# sensor_board.net
KiCad netlist of a schematic drawn in EAGLE
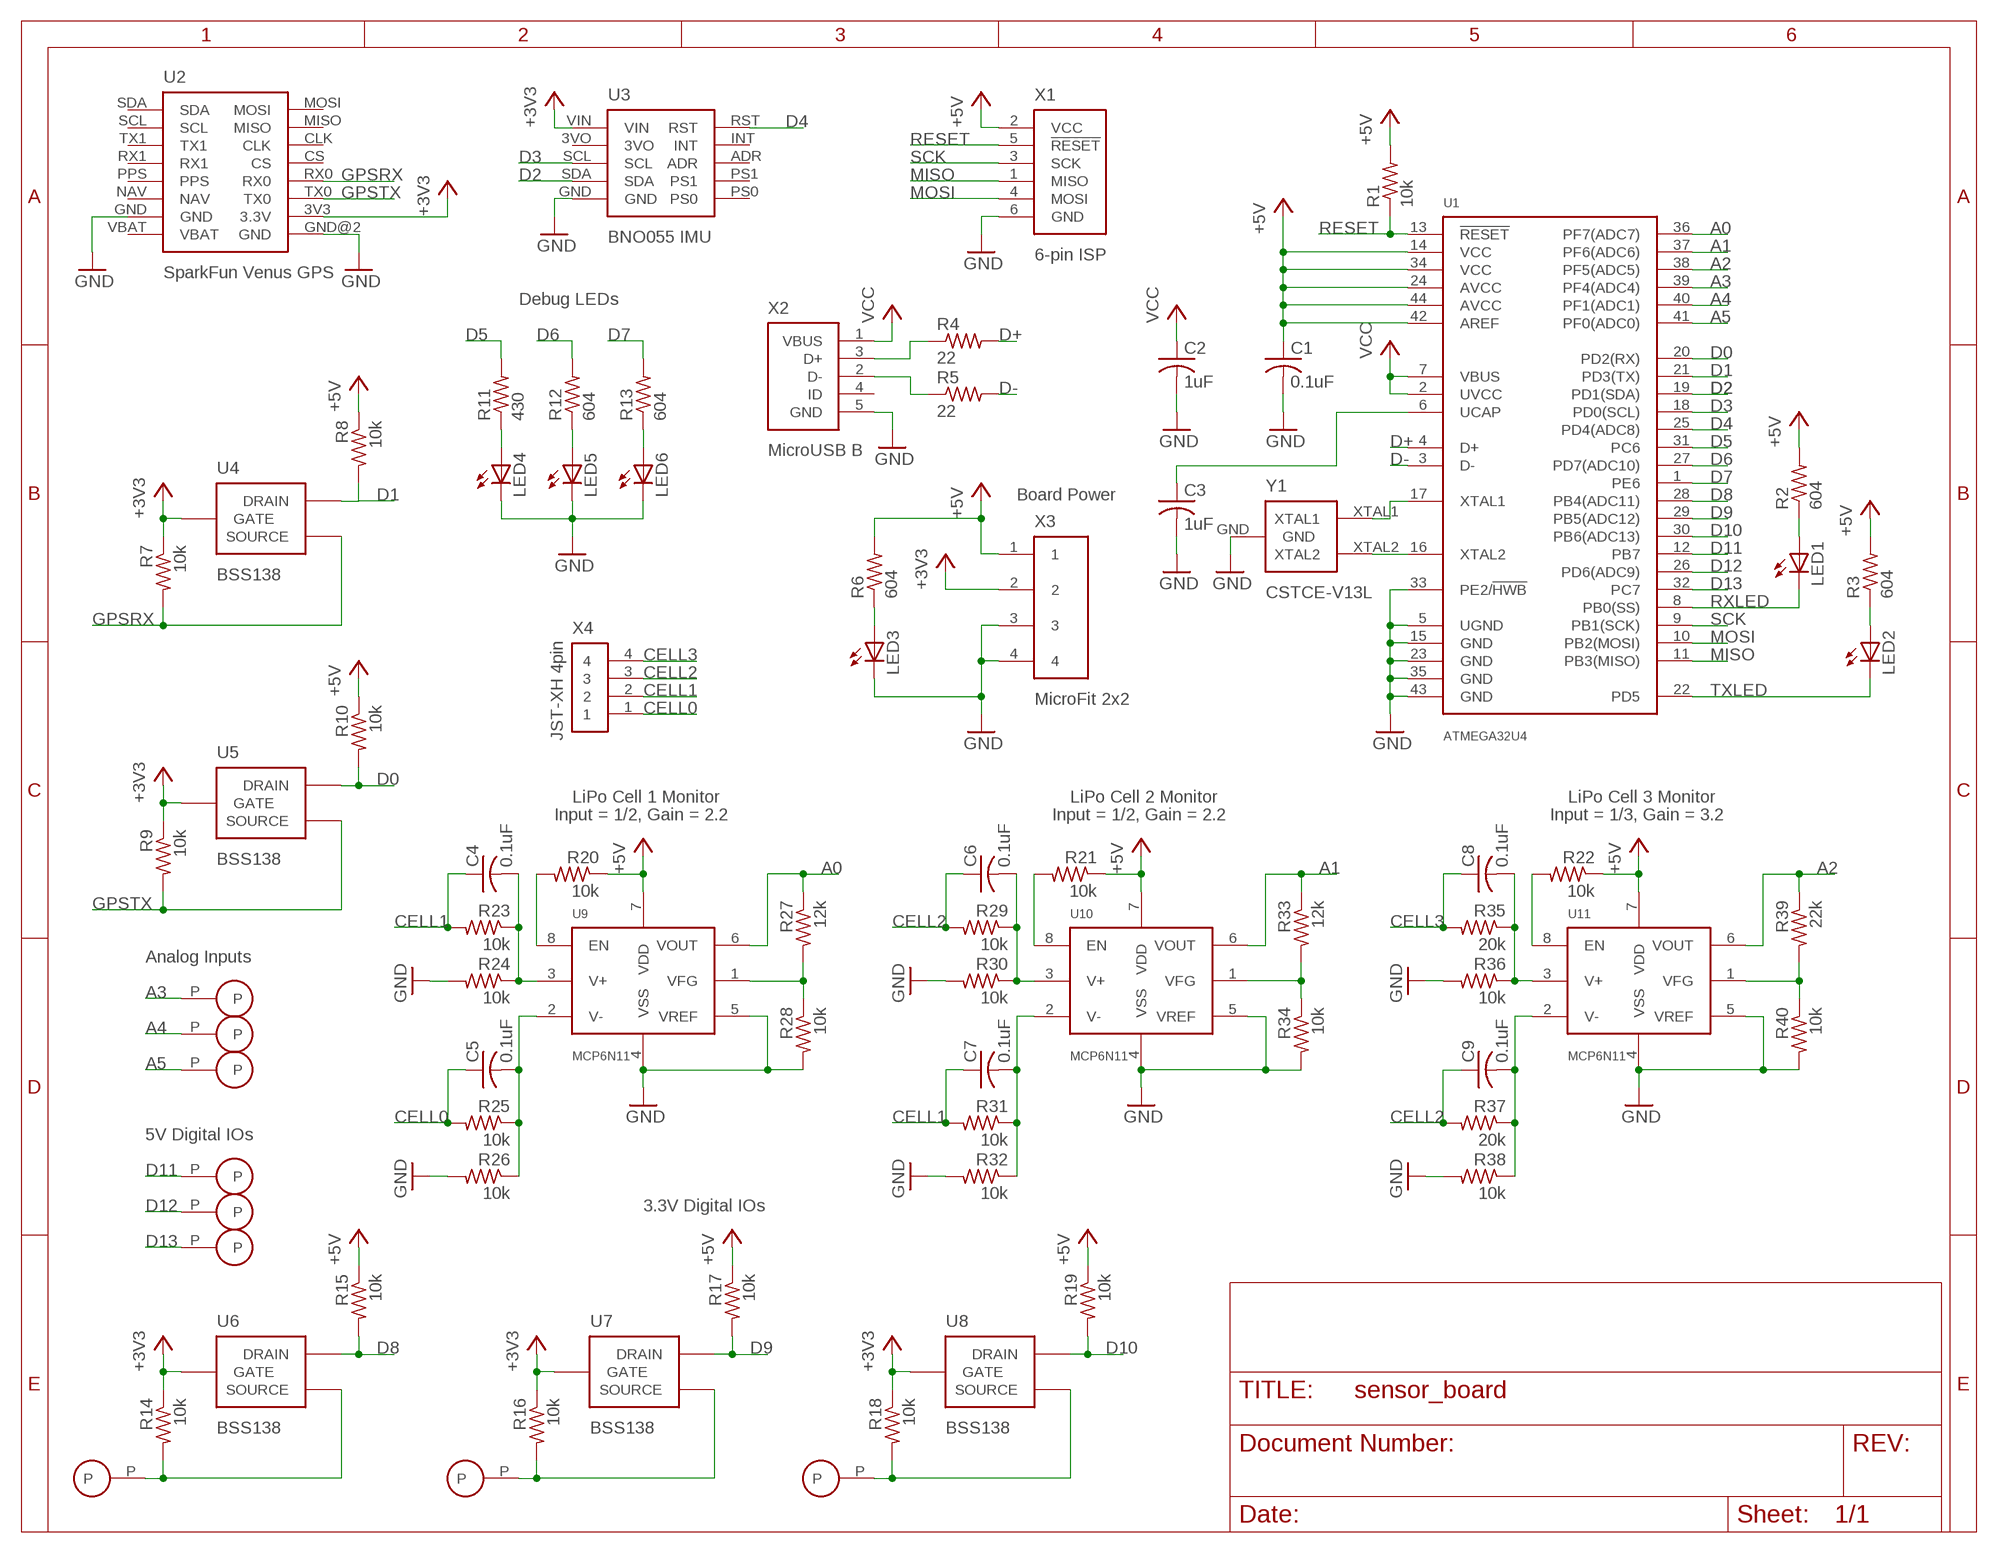
[diagram p0: schematic, sheet 1]

(export (version "E")
  (design (tool "Eeschema 10.0.6"))
  (components
    (comp (ref "C1")
      (value "0.1uF")
      (footprint "eagle-import:C0603")
      (libsource (lib "eagle-import") (part "C-USC0603"))
    )
    (comp (ref "C2")
      (value "1uF")
      (footprint "eagle-import:C0603")
      (libsource (lib "eagle-import") (part "C-USC0603"))
    )
    (comp (ref "C3")
      (value "1uF")
      (footprint "eagle-import:C0603")
      (libsource (lib "eagle-import") (part "C-USC0603"))
    )
    (comp (ref "C4")
      (value "0.1uF")
      (footprint "eagle-import:C0603")
      (libsource (lib "eagle-import") (part "C-USC0603"))
    )
    (comp (ref "C5")
      (value "0.1uF")
      (footprint "eagle-import:C0603")
      (libsource (lib "eagle-import") (part "C-USC0603"))
    )
    (comp (ref "C6")
      (value "0.1uF")
      (footprint "eagle-import:C0603")
      (libsource (lib "eagle-import") (part "C-USC0603"))
    )
    (comp (ref "C7")
      (value "0.1uF")
      (footprint "eagle-import:C0603")
      (libsource (lib "eagle-import") (part "C-USC0603"))
    )
    (comp (ref "C8")
      (value "0.1uF")
      (footprint "eagle-import:C0603")
      (libsource (lib "eagle-import") (part "C-USC0603"))
    )
    (comp (ref "C9")
      (value "0.1uF")
      (footprint "eagle-import:C0603")
      (libsource (lib "eagle-import") (part "C-USC0603"))
    )
    (comp (ref "LED1")
      (value "LEDCHIPLED_0603")
      (footprint "eagle-import:CHIPLED_0603")
      (libsource (lib "eagle-import") (part "LEDCHIPLED_0603"))
    )
    (comp (ref "LED2")
      (value "LEDCHIPLED_0603")
      (footprint "eagle-import:CHIPLED_0603")
      (libsource (lib "eagle-import") (part "LEDCHIPLED_0603"))
    )
    (comp (ref "LED3")
      (value "LEDCHIPLED_0603")
      (footprint "eagle-import:CHIPLED_0603")
      (libsource (lib "eagle-import") (part "LEDCHIPLED_0603"))
    )
    (comp (ref "LED4")
      (value "LEDCHIPLED_0603")
      (footprint "eagle-import:CHIPLED_0603")
      (libsource (lib "eagle-import") (part "LEDCHIPLED_0603"))
    )
    (comp (ref "LED5")
      (value "LEDCHIPLED_0603")
      (footprint "eagle-import:CHIPLED_0603")
      (libsource (lib "eagle-import") (part "LEDCHIPLED_0603"))
    )
    (comp (ref "LED6")
      (value "LEDCHIPLED_0603")
      (footprint "eagle-import:CHIPLED_0603")
      (libsource (lib "eagle-import") (part "LEDCHIPLED_0603"))
    )
    (comp (ref "P1")
      (value "100MIL-PAD")
      (footprint "eagle-import:100MIL-PAD")
      (libsource (lib "eagle-import") (part "100MIL-PAD"))
    )
    (comp (ref "P2")
      (value "100MIL-PAD")
      (footprint "eagle-import:100MIL-PAD")
      (libsource (lib "eagle-import") (part "100MIL-PAD"))
    )
    (comp (ref "P3")
      (value "100MIL-PAD")
      (footprint "eagle-import:100MIL-PAD")
      (libsource (lib "eagle-import") (part "100MIL-PAD"))
    )
    (comp (ref "P4")
      (value "100MIL-PAD")
      (footprint "eagle-import:100MIL-PAD")
      (libsource (lib "eagle-import") (part "100MIL-PAD"))
    )
    (comp (ref "P5")
      (value "100MIL-PAD")
      (footprint "eagle-import:100MIL-PAD")
      (libsource (lib "eagle-import") (part "100MIL-PAD"))
    )
    (comp (ref "P6")
      (value "100MIL-PAD")
      (footprint "eagle-import:100MIL-PAD")
      (libsource (lib "eagle-import") (part "100MIL-PAD"))
    )
    (comp (ref "P8")
      (value "100MIL-PAD")
      (footprint "eagle-import:100MIL-PAD")
      (libsource (lib "eagle-import") (part "100MIL-PAD"))
    )
    (comp (ref "P9")
      (value "100MIL-PAD")
      (footprint "eagle-import:100MIL-PAD")
      (libsource (lib "eagle-import") (part "100MIL-PAD"))
    )
    (comp (ref "P10")
      (value "100MIL-PAD")
      (footprint "eagle-import:100MIL-PAD")
      (libsource (lib "eagle-import") (part "100MIL-PAD"))
    )
    (comp (ref "R1")
      (value "10k")
      (footprint "eagle-import:R0603")
      (libsource (lib "eagle-import") (part "R-US_R0603"))
    )
    (comp (ref "R2")
      (value "604")
      (footprint "eagle-import:R0603")
      (libsource (lib "eagle-import") (part "R-US_R0603"))
    )
    (comp (ref "R3")
      (value "604")
      (footprint "eagle-import:R0603")
      (libsource (lib "eagle-import") (part "R-US_R0603"))
    )
    (comp (ref "R4")
      (value "22")
      (footprint "eagle-import:R0603")
      (libsource (lib "eagle-import") (part "R-US_R0603"))
    )
    (comp (ref "R5")
      (value "22")
      (footprint "eagle-import:R0603")
      (libsource (lib "eagle-import") (part "R-US_R0603"))
    )
    (comp (ref "R6")
      (value "604")
      (footprint "eagle-import:R0603")
      (libsource (lib "eagle-import") (part "R-US_R0603"))
    )
    (comp (ref "R7")
      (value "10k")
      (footprint "eagle-import:R0603")
      (libsource (lib "eagle-import") (part "R-US_R0603"))
    )
    (comp (ref "R8")
      (value "10k")
      (footprint "eagle-import:R0603")
      (libsource (lib "eagle-import") (part "R-US_R0603"))
    )
    (comp (ref "R9")
      (value "10k")
      (footprint "eagle-import:R0603")
      (libsource (lib "eagle-import") (part "R-US_R0603"))
    )
    (comp (ref "R10")
      (value "10k")
      (footprint "eagle-import:R0603")
      (libsource (lib "eagle-import") (part "R-US_R0603"))
    )
    (comp (ref "R11")
      (value "430")
      (footprint "eagle-import:R0603")
      (libsource (lib "eagle-import") (part "R-US_R0603"))
    )
    (comp (ref "R12")
      (value "604")
      (footprint "eagle-import:R0603")
      (libsource (lib "eagle-import") (part "R-US_R0603"))
    )
    (comp (ref "R13")
      (value "604")
      (footprint "eagle-import:R0603")
      (libsource (lib "eagle-import") (part "R-US_R0603"))
    )
    (comp (ref "R14")
      (value "10k")
      (footprint "eagle-import:R0603")
      (libsource (lib "eagle-import") (part "R-US_R0603"))
    )
    (comp (ref "R15")
      (value "10k")
      (footprint "eagle-import:R0603")
      (libsource (lib "eagle-import") (part "R-US_R0603"))
    )
    (comp (ref "R16")
      (value "10k")
      (footprint "eagle-import:R0603")
      (libsource (lib "eagle-import") (part "R-US_R0603"))
    )
    (comp (ref "R17")
      (value "10k")
      (footprint "eagle-import:R0603")
      (libsource (lib "eagle-import") (part "R-US_R0603"))
    )
    (comp (ref "R18")
      (value "10k")
      (footprint "eagle-import:R0603")
      (libsource (lib "eagle-import") (part "R-US_R0603"))
    )
    (comp (ref "R19")
      (value "10k")
      (footprint "eagle-import:R0603")
      (libsource (lib "eagle-import") (part "R-US_R0603"))
    )
    (comp (ref "R20")
      (value "10k")
      (footprint "eagle-import:R0603")
      (libsource (lib "eagle-import") (part "R-US_R0603"))
    )
    (comp (ref "R21")
      (value "10k")
      (footprint "eagle-import:R0603")
      (libsource (lib "eagle-import") (part "R-US_R0603"))
    )
    (comp (ref "R22")
      (value "10k")
      (footprint "eagle-import:R0603")
      (libsource (lib "eagle-import") (part "R-US_R0603"))
    )
    (comp (ref "R23")
      (value "10k")
      (footprint "eagle-import:R0603")
      (libsource (lib "eagle-import") (part "R-US_R0603"))
    )
    (comp (ref "R24")
      (value "10k")
      (footprint "eagle-import:R0603")
      (libsource (lib "eagle-import") (part "R-US_R0603"))
    )
    (comp (ref "R25")
      (value "10k")
      (footprint "eagle-import:R0603")
      (libsource (lib "eagle-import") (part "R-US_R0603"))
    )
    (comp (ref "R26")
      (value "10k")
      (footprint "eagle-import:R0603")
      (libsource (lib "eagle-import") (part "R-US_R0603"))
    )
    (comp (ref "R27")
      (value "12k")
      (footprint "eagle-import:R0603")
      (libsource (lib "eagle-import") (part "R-US_R0603"))
    )
    (comp (ref "R28")
      (value "10k")
      (footprint "eagle-import:R0603")
      (libsource (lib "eagle-import") (part "R-US_R0603"))
    )
    (comp (ref "R29")
      (value "10k")
      (footprint "eagle-import:R0603")
      (libsource (lib "eagle-import") (part "R-US_R0603"))
    )
    (comp (ref "R30")
      (value "10k")
      (footprint "eagle-import:R0603")
      (libsource (lib "eagle-import") (part "R-US_R0603"))
    )
    (comp (ref "R31")
      (value "10k")
      (footprint "eagle-import:R0603")
      (libsource (lib "eagle-import") (part "R-US_R0603"))
    )
    (comp (ref "R32")
      (value "10k")
      (footprint "eagle-import:R0603")
      (libsource (lib "eagle-import") (part "R-US_R0603"))
    )
    (comp (ref "R33")
      (value "12k")
      (footprint "eagle-import:R0603")
      (libsource (lib "eagle-import") (part "R-US_R0603"))
    )
    (comp (ref "R34")
      (value "10k")
      (footprint "eagle-import:R0603")
      (libsource (lib "eagle-import") (part "R-US_R0603"))
    )
    (comp (ref "R35")
      (value "20k")
      (footprint "eagle-import:R0603")
      (libsource (lib "eagle-import") (part "R-US_R0603"))
    )
    (comp (ref "R36")
      (value "10k")
      (footprint "eagle-import:R0603")
      (libsource (lib "eagle-import") (part "R-US_R0603"))
    )
    (comp (ref "R37")
      (value "20k")
      (footprint "eagle-import:R0603")
      (libsource (lib "eagle-import") (part "R-US_R0603"))
    )
    (comp (ref "R38")
      (value "10k")
      (footprint "eagle-import:R0603")
      (libsource (lib "eagle-import") (part "R-US_R0603"))
    )
    (comp (ref "R39")
      (value "22k")
      (footprint "eagle-import:R0603")
      (libsource (lib "eagle-import") (part "R-US_R0603"))
    )
    (comp (ref "R40")
      (value "10k")
      (footprint "eagle-import:R0603")
      (libsource (lib "eagle-import") (part "R-US_R0603"))
    )
    (comp (ref "U1")
      (value "ATMEGA32U4")
      (footprint "eagle-import:TQFP-44")
      (libsource (lib "eagle-import") (part "ATMEGA32U4"))
    )
    (comp (ref "U2")
      (value "SPARKFUN-VENUS-GPS")
      (footprint "eagle-import:SPARKFUN-VENUS-GPS")
      (libsource (lib "eagle-import") (part "SPARKFUN-VENUS-GPS"))
    )
    (comp (ref "U3")
      (value "ADAFRUIT-BNO055-IMU")
      (footprint "eagle-import:ADAFRUIT-BNO055-IMU")
      (libsource (lib "eagle-import") (part "ADAFRUIT-BNO055-IMU"))
    )
    (comp (ref "U4")
      (value "BSS138")
      (footprint "eagle-import:SOT-23")
      (libsource (lib "eagle-import") (part "BSS138"))
    )
    (comp (ref "U5")
      (value "BSS138")
      (footprint "eagle-import:SOT-23")
      (libsource (lib "eagle-import") (part "BSS138"))
    )
    (comp (ref "U6")
      (value "BSS138")
      (footprint "eagle-import:SOT-23")
      (libsource (lib "eagle-import") (part "BSS138"))
    )
    (comp (ref "U7")
      (value "BSS138")
      (footprint "eagle-import:SOT-23")
      (libsource (lib "eagle-import") (part "BSS138"))
    )
    (comp (ref "U8")
      (value "BSS138")
      (footprint "eagle-import:SOT-23")
      (libsource (lib "eagle-import") (part "BSS138"))
    )
    (comp (ref "U9")
      (value "MCP6N11")
      (footprint "eagle-import:SOIC-8")
      (libsource (lib "eagle-import") (part "MCP6N11"))
    )
    (comp (ref "U10")
      (value "MCP6N11")
      (footprint "eagle-import:SOIC-8")
      (libsource (lib "eagle-import") (part "MCP6N11"))
    )
    (comp (ref "U11")
      (value "MCP6N11")
      (footprint "eagle-import:SOIC-8")
      (libsource (lib "eagle-import") (part "MCP6N11"))
    )
    (comp (ref "X1")
      (value "ISP-HEADER")
      (footprint "eagle-import:ISP-HEADER")
      (libsource (lib "eagle-import") (part "ISP-HEADER"))
    )
    (comp (ref "X2")
      (value "MICRO-USB-B")
      (footprint "eagle-import:MICRO-USB-B")
      (libsource (lib "eagle-import") (part "MICRO-USB-B"))
    )
    (comp (ref "X3")
      (value "MICROFIT-2X2-SMD")
      (footprint "eagle-import:MICROFIT-2X2-0430450411")
      (libsource (lib "eagle-import") (part "MICROFIT-2X2-SMD"))
    )
    (comp (ref "X4")
      (value "JST-XH-4")
      (footprint "eagle-import:JST-XH-4")
      (libsource (lib "eagle-import") (part "JST-XH-4"))
    )
    (comp (ref "Y1")
      (value "CSTCE-V13L")
      (footprint "eagle-import:CSTCE-V13L")
      (libsource (lib "eagle-import") (part "CSTCE-V13L"))
    )
  )
  (nets
    (net (code "1") (name "+3V3") (class "Default")
      (node (ref "R14") (pin "1") (pinfunction "1_1") (pintype "passive"))
      (node (ref "R16") (pin "1") (pinfunction "1_1") (pintype "passive"))
      (node (ref "R18") (pin "1") (pinfunction "1_1") (pintype "passive"))
      (node (ref "R7") (pin "1") (pinfunction "1_1") (pintype "passive"))
      (node (ref "R9") (pin "1") (pinfunction "1_1") (pintype "passive"))
      (node (ref "U2") (pin "3V3") (pinfunction "3.3V_3V3") (pintype "power_in"))
      (node (ref "U3") (pin "VIN") (pinfunction "VIN_VIN") (pintype "power_in"))
      (node (ref "U4") (pin "GATE") (pinfunction "GATE_GATE") (pintype "bidirectional"))
      (node (ref "U5") (pin "GATE") (pinfunction "GATE_GATE") (pintype "bidirectional"))
      (node (ref "U6") (pin "GATE") (pinfunction "GATE_GATE") (pintype "bidirectional"))
      (node (ref "U7") (pin "GATE") (pinfunction "GATE_GATE") (pintype "bidirectional"))
      (node (ref "U8") (pin "GATE") (pinfunction "GATE_GATE") (pintype "bidirectional"))
      (node (ref "X3") (pin "2") (pinfunction "2_2") (pintype "bidirectional"))
    )
    (net (code "2") (name "+5V") (class "Default")
      (node (ref "C1") (pin "1") (pinfunction "1_1") (pintype "passive"))
      (node (ref "R1") (pin "2") (pinfunction "2_2") (pintype "passive"))
      (node (ref "R10") (pin "1") (pinfunction "1_1") (pintype "passive"))
      (node (ref "R15") (pin "1") (pinfunction "1_1") (pintype "passive"))
      (node (ref "R17") (pin "1") (pinfunction "1_1") (pintype "passive"))
      (node (ref "R19") (pin "1") (pinfunction "1_1") (pintype "passive"))
      (node (ref "R2") (pin "2") (pinfunction "2_2") (pintype "passive"))
      (node (ref "R20") (pin "1") (pinfunction "1_1") (pintype "passive"))
      (node (ref "R21") (pin "1") (pinfunction "1_1") (pintype "passive"))
      (node (ref "R22") (pin "1") (pinfunction "1_1") (pintype "passive"))
      (node (ref "R3") (pin "2") (pinfunction "2_2") (pintype "passive"))
      (node (ref "R6") (pin "2") (pinfunction "2_2") (pintype "passive"))
      (node (ref "R8") (pin "1") (pinfunction "1_1") (pintype "passive"))
      (node (ref "U1") (pin "14") (pinfunction "VCC_14") (pintype "power_in"))
      (node (ref "U1") (pin "24") (pinfunction "AVCC_24") (pintype "power_in"))
      (node (ref "U1") (pin "34") (pinfunction "VCC_34") (pintype "power_in"))
      (node (ref "U1") (pin "42") (pinfunction "AREF_42") (pintype "input"))
      (node (ref "U1") (pin "44") (pinfunction "AVCC_44") (pintype "power_in"))
      (node (ref "U10") (pin "7") (pinfunction "VDD_7") (pintype "power_in"))
      (node (ref "U11") (pin "7") (pinfunction "VDD_7") (pintype "power_in"))
      (node (ref "U9") (pin "7") (pinfunction "VDD_7") (pintype "power_in"))
      (node (ref "X1") (pin "2") (pinfunction "VCC_2") (pintype "power_in"))
      (node (ref "X3") (pin "1") (pinfunction "1_1") (pintype "bidirectional"))
    )
    (net (code "3") (name "/3VO") (class "Default")
      (node (ref "U3") (pin "3VO") (pinfunction "3VO_3VO") (pintype "power_in"))
    )
    (net (code "4") (name "/A0") (class "Default")
      (node (ref "R27") (pin "1") (pinfunction "1_1") (pintype "passive"))
      (node (ref "U1") (pin "36") (pinfunction "PF7(ADC7)_36") (pintype "bidirectional"))
      (node (ref "U9") (pin "6") (pinfunction "VOUT_6") (pintype "bidirectional"))
    )
    (net (code "5") (name "/A1") (class "Default")
      (node (ref "R33") (pin "1") (pinfunction "1_1") (pintype "passive"))
      (node (ref "U1") (pin "37") (pinfunction "PF6(ADC6)_37") (pintype "bidirectional"))
      (node (ref "U10") (pin "6") (pinfunction "VOUT_6") (pintype "bidirectional"))
    )
    (net (code "6") (name "/A2") (class "Default")
      (node (ref "R39") (pin "1") (pinfunction "1_1") (pintype "passive"))
      (node (ref "U1") (pin "38") (pinfunction "PF5(ADC5)_38") (pintype "bidirectional"))
      (node (ref "U11") (pin "6") (pinfunction "VOUT_6") (pintype "bidirectional"))
    )
    (net (code "7") (name "/A3") (class "Default")
      (node (ref "P8") (pin "P") (pinfunction "P_P") (pintype "bidirectional"))
      (node (ref "U1") (pin "39") (pinfunction "PF4(ADC4)_39") (pintype "bidirectional"))
    )
    (net (code "8") (name "/A4") (class "Default")
      (node (ref "P9") (pin "P") (pinfunction "P_P") (pintype "bidirectional"))
      (node (ref "U1") (pin "40") (pinfunction "PF1(ADC1)_40") (pintype "bidirectional"))
    )
    (net (code "9") (name "/A5") (class "Default")
      (node (ref "P10") (pin "P") (pinfunction "P_P") (pintype "bidirectional"))
      (node (ref "U1") (pin "41") (pinfunction "PF0(ADC0)_41") (pintype "bidirectional"))
    )
    (net (code "10") (name "/CELL0") (class "Default")
      (node (ref "C5") (pin "1") (pinfunction "1_1") (pintype "passive"))
      (node (ref "R25") (pin "2") (pinfunction "2_2") (pintype "passive"))
      (node (ref "X4") (pin "1") (pinfunction "1_1") (pintype "bidirectional"))
    )
    (net (code "11") (name "/CELL1") (class "Default")
      (node (ref "C4") (pin "1") (pinfunction "1_1") (pintype "passive"))
      (node (ref "C7") (pin "1") (pinfunction "1_1") (pintype "passive"))
      (node (ref "R23") (pin "2") (pinfunction "2_2") (pintype "passive"))
      (node (ref "R31") (pin "2") (pinfunction "2_2") (pintype "passive"))
      (node (ref "X4") (pin "2") (pinfunction "2_2") (pintype "bidirectional"))
    )
    (net (code "12") (name "/CELL2") (class "Default")
      (node (ref "C6") (pin "1") (pinfunction "1_1") (pintype "passive"))
      (node (ref "C9") (pin "1") (pinfunction "1_1") (pintype "passive"))
      (node (ref "R29") (pin "2") (pinfunction "2_2") (pintype "passive"))
      (node (ref "R37") (pin "2") (pinfunction "2_2") (pintype "passive"))
      (node (ref "X4") (pin "3") (pinfunction "3_3") (pintype "bidirectional"))
    )
    (net (code "13") (name "/CELL3") (class "Default")
      (node (ref "C8") (pin "1") (pinfunction "1_1") (pintype "passive"))
      (node (ref "R35") (pin "2") (pinfunction "2_2") (pintype "passive"))
      (node (ref "X4") (pin "4") (pinfunction "4_4") (pintype "bidirectional"))
    )
    (net (code "14") (name "/D+") (class "Default")
      (node (ref "R4") (pin "2") (pinfunction "2_2") (pintype "passive"))
      (node (ref "U1") (pin "4") (pinfunction "D+_4") (pintype "bidirectional"))
    )
    (net (code "15") (name "/D-") (class "Default")
      (node (ref "R5") (pin "2") (pinfunction "2_2") (pintype "passive"))
      (node (ref "U1") (pin "3") (pinfunction "D-_3") (pintype "bidirectional"))
    )
    (net (code "16") (name "/D0") (class "Default")
      (node (ref "R10") (pin "2") (pinfunction "2_2") (pintype "passive"))
      (node (ref "U1") (pin "20") (pinfunction "PD2(RX)_20") (pintype "bidirectional"))
      (node (ref "U5") (pin "DRAIN") (pinfunction "DRAIN_DRAIN") (pintype "bidirectional"))
    )
    (net (code "17") (name "/D1") (class "Default")
      (node (ref "R8") (pin "2") (pinfunction "2_2") (pintype "passive"))
      (node (ref "U1") (pin "21") (pinfunction "PD3(TX)_21") (pintype "bidirectional"))
      (node (ref "U4") (pin "DRAIN") (pinfunction "DRAIN_DRAIN") (pintype "bidirectional"))
    )
    (net (code "18") (name "/D2") (class "Default")
      (node (ref "U1") (pin "19") (pinfunction "PD1(SDA)_19") (pintype "bidirectional"))
      (node (ref "U3") (pin "SDA") (pinfunction "SDA_SDA") (pintype "bidirectional"))
    )
    (net (code "19") (name "/D3") (class "Default")
      (node (ref "U1") (pin "18") (pinfunction "PD0(SCL)_18") (pintype "bidirectional"))
      (node (ref "U3") (pin "SCL") (pinfunction "SCL_SCL") (pintype "bidirectional"))
    )
    (net (code "20") (name "/D4") (class "Default")
      (node (ref "U1") (pin "25") (pinfunction "PD4(ADC8)_25") (pintype "bidirectional"))
      (node (ref "U3") (pin "RST") (pinfunction "RST_RST") (pintype "bidirectional"))
    )
    (net (code "21") (name "/D5") (class "Default")
      (node (ref "R11") (pin "2") (pinfunction "2_2") (pintype "passive"))
      (node (ref "U1") (pin "31") (pinfunction "PC6_31") (pintype "bidirectional"))
    )
    (net (code "22") (name "/D6") (class "Default")
      (node (ref "R12") (pin "2") (pinfunction "2_2") (pintype "passive"))
      (node (ref "U1") (pin "27") (pinfunction "PD7(ADC10)_27") (pintype "bidirectional"))
    )
    (net (code "23") (name "/D7") (class "Default")
      (node (ref "R13") (pin "2") (pinfunction "2_2") (pintype "passive"))
      (node (ref "U1") (pin "1") (pinfunction "PE6_1") (pintype "bidirectional"))
    )
    (net (code "24") (name "/D8") (class "Default")
      (node (ref "R15") (pin "2") (pinfunction "2_2") (pintype "passive"))
      (node (ref "U1") (pin "28") (pinfunction "PB4(ADC11)_28") (pintype "bidirectional"))
      (node (ref "U6") (pin "DRAIN") (pinfunction "DRAIN_DRAIN") (pintype "bidirectional"))
    )
    (net (code "25") (name "/D9") (class "Default")
      (node (ref "R17") (pin "2") (pinfunction "2_2") (pintype "passive"))
      (node (ref "U1") (pin "29") (pinfunction "PB5(ADC12)_29") (pintype "bidirectional"))
      (node (ref "U7") (pin "DRAIN") (pinfunction "DRAIN_DRAIN") (pintype "bidirectional"))
    )
    (net (code "26") (name "/D10") (class "Default")
      (node (ref "R19") (pin "2") (pinfunction "2_2") (pintype "passive"))
      (node (ref "U1") (pin "30") (pinfunction "PB6(ADC13)_30") (pintype "bidirectional"))
      (node (ref "U8") (pin "DRAIN") (pinfunction "DRAIN_DRAIN") (pintype "bidirectional"))
    )
    (net (code "27") (name "/D11") (class "Default")
      (node (ref "P1") (pin "P") (pinfunction "P_P") (pintype "bidirectional"))
      (node (ref "U1") (pin "12") (pinfunction "PB7_12") (pintype "bidirectional"))
    )
    (net (code "28") (name "/D12") (class "Default")
      (node (ref "P2") (pin "P") (pinfunction "P_P") (pintype "bidirectional"))
      (node (ref "U1") (pin "26") (pinfunction "PD6(ADC9)_26") (pintype "bidirectional"))
    )
    (net (code "29") (name "/D13") (class "Default")
      (node (ref "P3") (pin "P") (pinfunction "P_P") (pintype "bidirectional"))
      (node (ref "U1") (pin "32") (pinfunction "PC7_32") (pintype "bidirectional"))
    )
    (net (code "30") (name "/GPSRX") (class "Default")
      (node (ref "R7") (pin "2") (pinfunction "2_2") (pintype "passive"))
      (node (ref "U2") (pin "RX0") (pinfunction "RX0_RX0") (pintype "bidirectional"))
      (node (ref "U4") (pin "SOURCE") (pinfunction "SOURCE_SOURCE") (pintype "bidirectional"))
    )
    (net (code "31") (name "/GPSTX") (class "Default")
      (node (ref "R9") (pin "2") (pinfunction "2_2") (pintype "passive"))
      (node (ref "U2") (pin "TX0") (pinfunction "TX0_TX0") (pintype "bidirectional"))
      (node (ref "U5") (pin "SOURCE") (pinfunction "SOURCE_SOURCE") (pintype "bidirectional"))
    )
    (net (code "32") (name "/MISO") (class "Default")
      (node (ref "U1") (pin "11") (pinfunction "PB3(MISO)_11") (pintype "bidirectional"))
      (node (ref "X1") (pin "1") (pinfunction "MISO_1") (pintype "bidirectional"))
    )
    (net (code "33") (name "/MOSI") (class "Default")
      (node (ref "U1") (pin "10") (pinfunction "PB2(MOSI)_10") (pintype "bidirectional"))
      (node (ref "X1") (pin "4") (pinfunction "MOSI_4") (pintype "bidirectional"))
    )
    (net (code "34") (name "/RESET") (class "Default")
      (node (ref "R1") (pin "1") (pinfunction "1_1") (pintype "passive"))
      (node (ref "U1") (pin "13") (pinfunction "~{RESET}_13") (pintype "input"))
      (node (ref "X1") (pin "5") (pinfunction "~{RESET}_5") (pintype "bidirectional"))
    )
    (net (code "35") (name "/RXLED") (class "Default")
      (node (ref "LED1") (pin "C") (pinfunction "C_C") (pintype "passive"))
      (node (ref "U1") (pin "8") (pinfunction "PB0(SS)_8") (pintype "bidirectional"))
    )
    (net (code "36") (name "/SCK") (class "Default")
      (node (ref "U1") (pin "9") (pinfunction "PB1(SCK)_9") (pintype "bidirectional"))
      (node (ref "X1") (pin "3") (pinfunction "SCK_3") (pintype "bidirectional"))
    )
    (net (code "37") (name "/TXLED") (class "Default")
      (node (ref "LED2") (pin "C") (pinfunction "C_C") (pintype "passive"))
      (node (ref "U1") (pin "22") (pinfunction "PD5_22") (pintype "bidirectional"))
    )
    (net (code "38") (name "/VBAT") (class "Default")
      (node (ref "U2") (pin "VBAT") (pinfunction "VBAT_VBAT") (pintype "power_in"))
    )
    (net (code "39") (name "GND") (class "Default")
      (node (ref "C1") (pin "2") (pinfunction "2_2") (pintype "passive"))
      (node (ref "C2") (pin "2") (pinfunction "2_2") (pintype "passive"))
      (node (ref "C3") (pin "2") (pinfunction "2_2") (pintype "passive"))
      (node (ref "LED3") (pin "C") (pinfunction "C_C") (pintype "passive"))
      (node (ref "LED4") (pin "C") (pinfunction "C_C") (pintype "passive"))
      (node (ref "LED5") (pin "C") (pinfunction "C_C") (pintype "passive"))
      (node (ref "LED6") (pin "C") (pinfunction "C_C") (pintype "passive"))
      (node (ref "R24") (pin "2") (pinfunction "2_2") (pintype "passive"))
      (node (ref "R26") (pin "2") (pinfunction "2_2") (pintype "passive"))
      (node (ref "R28") (pin "2") (pinfunction "2_2") (pintype "passive"))
      (node (ref "R30") (pin "2") (pinfunction "2_2") (pintype "passive"))
      (node (ref "R32") (pin "2") (pinfunction "2_2") (pintype "passive"))
      (node (ref "R34") (pin "2") (pinfunction "2_2") (pintype "passive"))
      (node (ref "R36") (pin "2") (pinfunction "2_2") (pintype "passive"))
      (node (ref "R38") (pin "2") (pinfunction "2_2") (pintype "passive"))
      (node (ref "R40") (pin "2") (pinfunction "2_2") (pintype "passive"))
      (node (ref "U1") (pin "15") (pinfunction "GND_15") (pintype "power_in"))
      (node (ref "U1") (pin "23") (pinfunction "GND_23") (pintype "power_in"))
      (node (ref "U1") (pin "33") (pinfunction "PE2/~{HWB}_33") (pintype "bidirectional"))
      (node (ref "U1") (pin "35") (pinfunction "GND_35") (pintype "power_in"))
      (node (ref "U1") (pin "43") (pinfunction "GND_43") (pintype "power_in"))
      (node (ref "U1") (pin "5") (pinfunction "UGND_5") (pintype "power_in"))
      (node (ref "U10") (pin "4") (pinfunction "VSS_4") (pintype "power_in"))
      (node (ref "U10") (pin "5") (pinfunction "VREF_5") (pintype "bidirectional"))
      (node (ref "U11") (pin "4") (pinfunction "VSS_4") (pintype "power_in"))
      (node (ref "U11") (pin "5") (pinfunction "VREF_5") (pintype "bidirectional"))
      (node (ref "U2") (pin "GND") (pinfunction "GND_GND") (pintype "power_in"))
      (node (ref "U2") (pin "GND@2") (pinfunction "GND_GND@2") (pintype "power_in"))
      (node (ref "U3") (pin "GND") (pinfunction "GND_GND") (pintype "power_in"))
      (node (ref "U9") (pin "4") (pinfunction "VSS_4") (pintype "power_in"))
      (node (ref "U9") (pin "5") (pinfunction "VREF_5") (pintype "bidirectional"))
      (node (ref "X1") (pin "6") (pinfunction "GND_6") (pintype "power_in"))
      (node (ref "X2") (pin "5") (pinfunction "GND_5") (pintype "power_in"))
      (node (ref "X3") (pin "3") (pinfunction "3_3") (pintype "bidirectional"))
      (node (ref "X3") (pin "4") (pinfunction "4_4") (pintype "bidirectional"))
      (node (ref "Y1") (pin "GND") (pinfunction "GND_GND") (pintype "power_in"))
    )
    (net (code "40") (name "Net-(LED1-PadA)") (class "Default")
      (node (ref "LED1") (pin "A") (pinfunction "A_A") (pintype "passive"))
      (node (ref "R2") (pin "1") (pinfunction "1_1") (pintype "passive"))
    )
    (net (code "41") (name "Net-(LED2-PadA)") (class "Default")
      (node (ref "LED2") (pin "A") (pinfunction "A_A") (pintype "passive"))
      (node (ref "R3") (pin "1") (pinfunction "1_1") (pintype "passive"))
    )
    (net (code "42") (name "Net-(LED3-PadA)") (class "Default")
      (node (ref "LED3") (pin "A") (pinfunction "A_A") (pintype "passive"))
      (node (ref "R6") (pin "1") (pinfunction "1_1") (pintype "passive"))
    )
    (net (code "43") (name "Net-(LED4-PadA)") (class "Default")
      (node (ref "LED4") (pin "A") (pinfunction "A_A") (pintype "passive"))
      (node (ref "R11") (pin "1") (pinfunction "1_1") (pintype "passive"))
    )
    (net (code "44") (name "Net-(LED5-PadA)") (class "Default")
      (node (ref "LED5") (pin "A") (pinfunction "A_A") (pintype "passive"))
      (node (ref "R12") (pin "1") (pinfunction "1_1") (pintype "passive"))
    )
    (net (code "45") (name "Net-(LED6-PadA)") (class "Default")
      (node (ref "LED6") (pin "A") (pinfunction "A_A") (pintype "passive"))
      (node (ref "R13") (pin "1") (pinfunction "1_1") (pintype "passive"))
    )
    (net (code "46") (name "Net-(P4-PadP)") (class "Default")
      (node (ref "P4") (pin "P") (pinfunction "P_P") (pintype "bidirectional"))
      (node (ref "R14") (pin "2") (pinfunction "2_2") (pintype "passive"))
      (node (ref "U6") (pin "SOURCE") (pinfunction "SOURCE_SOURCE") (pintype "bidirectional"))
    )
    (net (code "47") (name "Net-(P5-PadP)") (class "Default")
      (node (ref "P5") (pin "P") (pinfunction "P_P") (pintype "bidirectional"))
      (node (ref "R16") (pin "2") (pinfunction "2_2") (pintype "passive"))
      (node (ref "U7") (pin "SOURCE") (pinfunction "SOURCE_SOURCE") (pintype "bidirectional"))
    )
    (net (code "48") (name "Net-(P6-PadP)") (class "Default")
      (node (ref "P6") (pin "P") (pinfunction "P_P") (pintype "bidirectional"))
      (node (ref "R18") (pin "2") (pinfunction "2_2") (pintype "passive"))
      (node (ref "U8") (pin "SOURCE") (pinfunction "SOURCE_SOURCE") (pintype "bidirectional"))
    )
    (net (code "49") (name "Net-(U1-UCAP)") (class "Default")
      (node (ref "C3") (pin "1") (pinfunction "1_1") (pintype "passive"))
      (node (ref "U1") (pin "6") (pinfunction "UCAP_6") (pintype "bidirectional"))
    )
    (net (code "50") (name "Net-(U1-XTAL1)") (class "Default")
      (node (ref "U1") (pin "17") (pinfunction "XTAL1_17") (pintype "bidirectional"))
      (node (ref "Y1") (pin "XTAL1") (pinfunction "XTAL1_XTAL1") (pintype "bidirectional"))
    )
    (net (code "51") (name "Net-(U1-XTAL2)") (class "Default")
      (node (ref "U1") (pin "16") (pinfunction "XTAL2_16") (pintype "bidirectional"))
      (node (ref "Y1") (pin "XTAL2") (pinfunction "XTAL2_XTAL2") (pintype "bidirectional"))
    )
    (net (code "52") (name "Net-(U9-EN)") (class "Default")
      (node (ref "R20") (pin "2") (pinfunction "2_2") (pintype "passive"))
      (node (ref "U9") (pin "8") (pinfunction "EN_8") (pintype "bidirectional"))
    )
    (net (code "53") (name "Net-(U9-V+)") (class "Default")
      (node (ref "C4") (pin "2") (pinfunction "2_2") (pintype "passive"))
      (node (ref "R23") (pin "1") (pinfunction "1_1") (pintype "passive"))
      (node (ref "R24") (pin "1") (pinfunction "1_1") (pintype "passive"))
      (node (ref "U9") (pin "3") (pinfunction "V+_3") (pintype "bidirectional"))
    )
    (net (code "54") (name "Net-(U9-V-)") (class "Default")
      (node (ref "C5") (pin "2") (pinfunction "2_2") (pintype "passive"))
      (node (ref "R25") (pin "1") (pinfunction "1_1") (pintype "passive"))
      (node (ref "R26") (pin "1") (pinfunction "1_1") (pintype "passive"))
      (node (ref "U9") (pin "2") (pinfunction "V-_2") (pintype "bidirectional"))
    )
    (net (code "55") (name "Net-(U9-VFG)") (class "Default")
      (node (ref "R27") (pin "2") (pinfunction "2_2") (pintype "passive"))
      (node (ref "R28") (pin "1") (pinfunction "1_1") (pintype "passive"))
      (node (ref "U9") (pin "1") (pinfunction "VFG_1") (pintype "bidirectional"))
    )
    (net (code "56") (name "Net-(U10-EN)") (class "Default")
      (node (ref "R21") (pin "2") (pinfunction "2_2") (pintype "passive"))
      (node (ref "U10") (pin "8") (pinfunction "EN_8") (pintype "bidirectional"))
    )
    (net (code "57") (name "Net-(U10-V+)") (class "Default")
      (node (ref "C6") (pin "2") (pinfunction "2_2") (pintype "passive"))
      (node (ref "R29") (pin "1") (pinfunction "1_1") (pintype "passive"))
      (node (ref "R30") (pin "1") (pinfunction "1_1") (pintype "passive"))
      (node (ref "U10") (pin "3") (pinfunction "V+_3") (pintype "bidirectional"))
    )
    (net (code "58") (name "Net-(U10-V-)") (class "Default")
      (node (ref "C7") (pin "2") (pinfunction "2_2") (pintype "passive"))
      (node (ref "R31") (pin "1") (pinfunction "1_1") (pintype "passive"))
      (node (ref "R32") (pin "1") (pinfunction "1_1") (pintype "passive"))
      (node (ref "U10") (pin "2") (pinfunction "V-_2") (pintype "bidirectional"))
    )
    (net (code "59") (name "Net-(U10-VFG)") (class "Default")
      (node (ref "R33") (pin "2") (pinfunction "2_2") (pintype "passive"))
      (node (ref "R34") (pin "1") (pinfunction "1_1") (pintype "passive"))
      (node (ref "U10") (pin "1") (pinfunction "VFG_1") (pintype "bidirectional"))
    )
    (net (code "60") (name "Net-(U11-EN)") (class "Default")
      (node (ref "R22") (pin "2") (pinfunction "2_2") (pintype "passive"))
      (node (ref "U11") (pin "8") (pinfunction "EN_8") (pintype "bidirectional"))
    )
    (net (code "61") (name "Net-(U11-V+)") (class "Default")
      (node (ref "C8") (pin "2") (pinfunction "2_2") (pintype "passive"))
      (node (ref "R35") (pin "1") (pinfunction "1_1") (pintype "passive"))
      (node (ref "R36") (pin "1") (pinfunction "1_1") (pintype "passive"))
      (node (ref "U11") (pin "3") (pinfunction "V+_3") (pintype "bidirectional"))
    )
    (net (code "62") (name "Net-(U11-V-)") (class "Default")
      (node (ref "C9") (pin "2") (pinfunction "2_2") (pintype "passive"))
      (node (ref "R37") (pin "1") (pinfunction "1_1") (pintype "passive"))
      (node (ref "R38") (pin "1") (pinfunction "1_1") (pintype "passive"))
      (node (ref "U11") (pin "2") (pinfunction "V-_2") (pintype "bidirectional"))
    )
    (net (code "63") (name "Net-(U11-VFG)") (class "Default")
      (node (ref "R39") (pin "2") (pinfunction "2_2") (pintype "passive"))
      (node (ref "R40") (pin "1") (pinfunction "1_1") (pintype "passive"))
      (node (ref "U11") (pin "1") (pinfunction "VFG_1") (pintype "bidirectional"))
    )
    (net (code "64") (name "Net-(X2-D+)") (class "Default")
      (node (ref "R4") (pin "1") (pinfunction "1_1") (pintype "passive"))
      (node (ref "X2") (pin "3") (pinfunction "D+_3") (pintype "bidirectional"))
    )
    (net (code "65") (name "Net-(X2-D-)") (class "Default")
      (node (ref "R5") (pin "1") (pinfunction "1_1") (pintype "passive"))
      (node (ref "X2") (pin "2") (pinfunction "D-_2") (pintype "bidirectional"))
    )
    (net (code "66") (name "VCC") (class "Default")
      (node (ref "C2") (pin "1") (pinfunction "1_1") (pintype "passive"))
      (node (ref "U1") (pin "2") (pinfunction "UVCC_2") (pintype "power_in"))
      (node (ref "U1") (pin "7") (pinfunction "VBUS_7") (pintype "power_in"))
      (node (ref "X2") (pin "1") (pinfunction "VBUS_1") (pintype "power_in"))
    )
    (net (code "67") (name "unconnected-(U2-PadCLK)") (class "Default")
      (node (ref "U2") (pin "CLK") (pinfunction "CLK_CLK") (pintype "bidirectional"))
    )
    (net (code "68") (name "unconnected-(U2-PadCS)") (class "Default")
      (node (ref "U2") (pin "CS") (pinfunction "CS_CS") (pintype "bidirectional"))
    )
    (net (code "69") (name "unconnected-(U2-PadMISO)") (class "Default")
      (node (ref "U2") (pin "MISO") (pinfunction "MISO_MISO") (pintype "bidirectional"))
    )
    (net (code "70") (name "unconnected-(U2-PadMOSI)") (class "Default")
      (node (ref "U2") (pin "MOSI") (pinfunction "MOSI_MOSI") (pintype "bidirectional"))
    )
    (net (code "71") (name "unconnected-(U2-PadNAV)") (class "Default")
      (node (ref "U2") (pin "NAV") (pinfunction "NAV_NAV") (pintype "bidirectional"))
    )
    (net (code "72") (name "unconnected-(U2-PadPPS)") (class "Default")
      (node (ref "U2") (pin "PPS") (pinfunction "PPS_PPS") (pintype "bidirectional"))
    )
    (net (code "73") (name "unconnected-(U2-PadRX1)") (class "Default")
      (node (ref "U2") (pin "RX1") (pinfunction "RX1_RX1") (pintype "bidirectional"))
    )
    (net (code "74") (name "unconnected-(U2-PadSCL)") (class "Default")
      (node (ref "U2") (pin "SCL") (pinfunction "SCL_SCL") (pintype "bidirectional"))
    )
    (net (code "75") (name "unconnected-(U2-PadSDA)") (class "Default")
      (node (ref "U2") (pin "SDA") (pinfunction "SDA_SDA") (pintype "bidirectional"))
    )
    (net (code "76") (name "unconnected-(U2-PadTX1)") (class "Default")
      (node (ref "U2") (pin "TX1") (pinfunction "TX1_TX1") (pintype "bidirectional"))
    )
    (net (code "77") (name "unconnected-(U3-PadADR)") (class "Default")
      (node (ref "U3") (pin "ADR") (pinfunction "ADR_ADR") (pintype "bidirectional"))
    )
    (net (code "78") (name "unconnected-(U3-PadINT)") (class "Default")
      (node (ref "U3") (pin "INT") (pinfunction "INT_INT") (pintype "bidirectional"))
    )
    (net (code "79") (name "unconnected-(U3-PadPS0)") (class "Default")
      (node (ref "U3") (pin "PS0") (pinfunction "PS0_PS0") (pintype "bidirectional"))
    )
    (net (code "80") (name "unconnected-(U3-PadPS1)") (class "Default")
      (node (ref "U3") (pin "PS1") (pinfunction "PS1_PS1") (pintype "bidirectional"))
    )
    (net (code "81") (name "unconnected-(X2-ID-Pad4)") (class "Default")
      (node (ref "X2") (pin "4") (pinfunction "ID_4") (pintype "bidirectional"))
    )
  )
)
